# Motor_Connection.net
KiCad netlist of a schematic drawn in Altium Designer
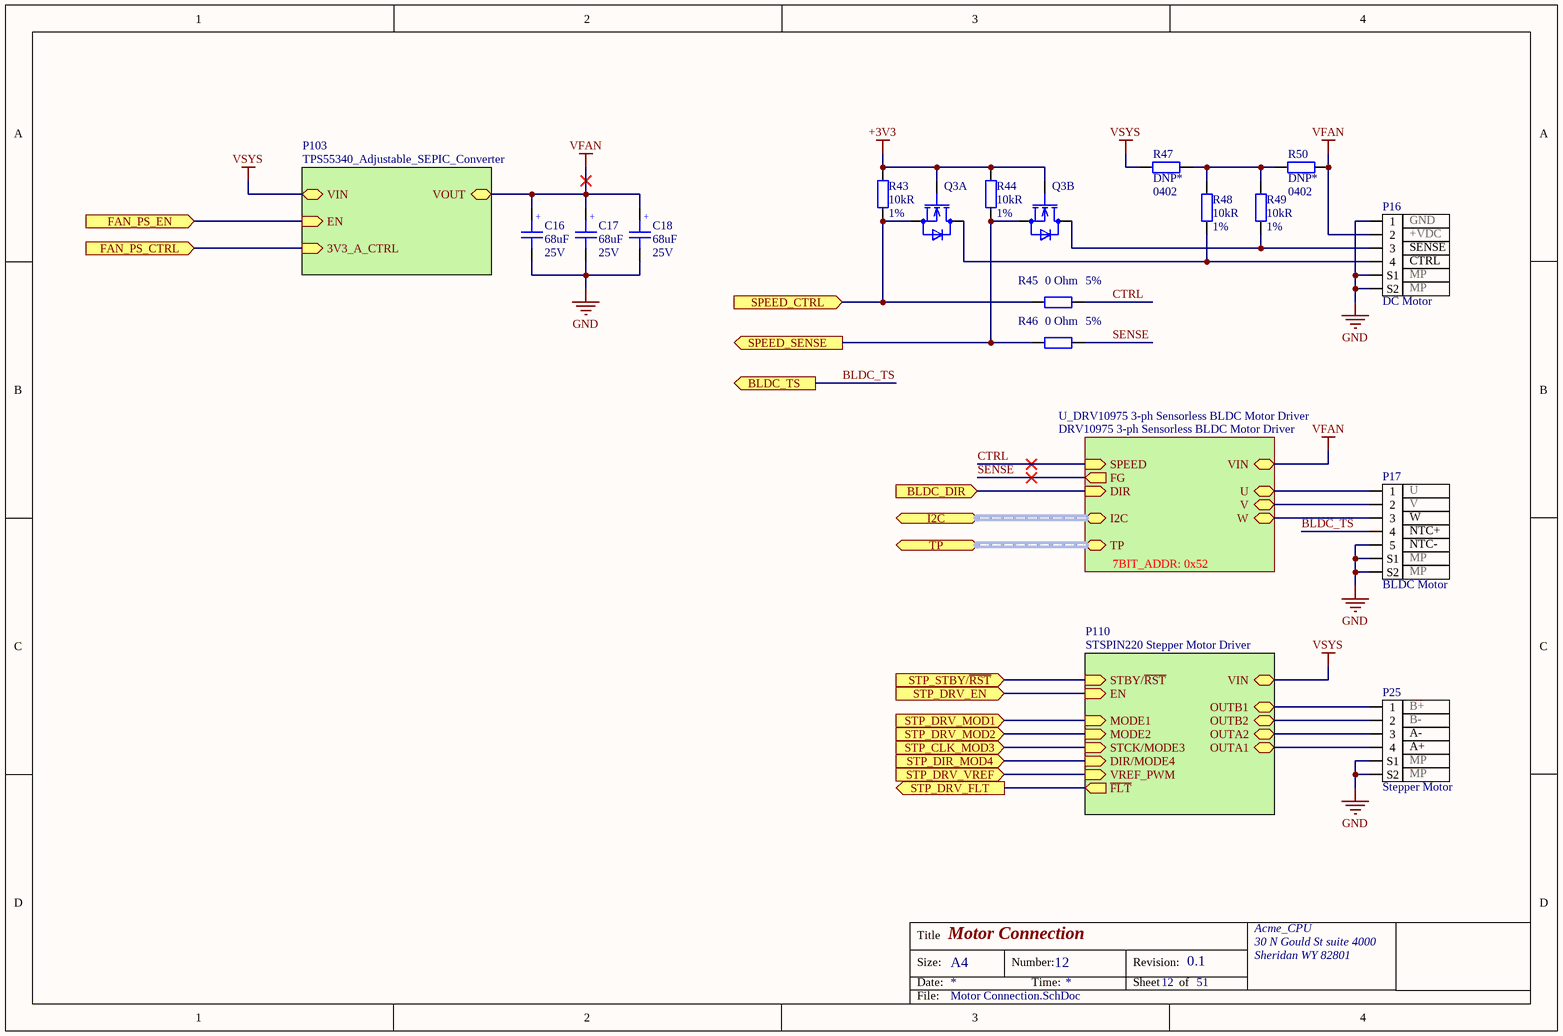
[diagram p0: Motor Connection.SchDoc]

(export (version "E")
  (design (tool "Eeschema 10.0.6"))
  (components
    (comp (ref "C16")
      (value "CAP ALUM 68 UF 20% 25 V SMD")
      (footprint "WCAP-ASLI_6.3x5.5")
      (description "68µF 25V Aluminum Electrolytic Capacitors Radial, Can - SMD  2000 Hrs @ 105°C")
      (fields
        (field (name "MANUFACTURER") "Wurth Elektronik")
        (field (name "MANUFACTURER PART NUMBER") "865080443009")
        (field (name "CAPACITANCE") "68uF")
        (field (name "RATED VOLTAGE") "25V")
      )
      (libsource (lib "capacitors_alum_electr_poly") (part "CAP ALUM 68 UF 20% 25 V SMD"))
    )
    (comp (ref "C17")
      (value "CAP ALUM 68 UF 20% 25 V SMD")
      (footprint "WCAP-ASLI_6.3x5.5")
      (description "68µF 25V Aluminum Electrolytic Capacitors Radial, Can - SMD  2000 Hrs @ 105°C")
      (fields
        (field (name "MANUFACTURER") "Wurth Elektronik")
        (field (name "MANUFACTURER PART NUMBER") "865080443009")
        (field (name "CAPACITANCE") "68uF")
        (field (name "RATED VOLTAGE") "25V")
      )
      (libsource (lib "capacitors_alum_electr_poly") (part "CAP ALUM 68 UF 20% 25 V SMD"))
    )
    (comp (ref "C18")
      (value "CAP ALUM 68 UF 20% 25 V SMD")
      (footprint "WCAP-ASLI_6.3x5.5")
      (description "68µF 25V Aluminum Electrolytic Capacitors Radial, Can - SMD  2000 Hrs @ 105°C")
      (fields
        (field (name "MANUFACTURER") "Wurth Elektronik")
        (field (name "MANUFACTURER PART NUMBER") "865080443009")
        (field (name "CAPACITANCE") "68uF")
        (field (name "RATED VOLTAGE") "25V")
      )
      (libsource (lib "capacitors_alum_electr_poly") (part "CAP ALUM 68 UF 20% 25 V SMD"))
    )
    (comp (ref "P16")
      (value "DC Motor")
      (footprint "CONN_JST_S4B-ZR-SM4A-TF(LF)(SN)")
      (description "Connector Header Surface Mount, Right Angle 4 position 0.059\" (1.50mm)")
      (fields
        (field (name "MANUFACTURER") "JST")
        (field (name "MANUFACTURER PART NUMBER") "S4B-ZR-SM4A-TF(LF)(SN)")
        (field (name "PIN_1") "GND")
        (field (name "PIN_2") "+VDC")
        (field (name "PIN_MP1") "MP")
        (field (name "PIN_MP2") "MP")
        (field (name "PIN_3") "SENSE")
        (field (name "PIN_4") "CTRL")
      )
      (libsource (lib "connectors_header") (part "CONN HEADER SMD R/A 4POS 1.5MM"))
    )
    (comp (ref "P17")
      (value "BLDC Motor")
      (footprint "CONN_JST_S5B-ZR-SM4A-TF(LF)(SN)")
      (description "Connector Header Surface Mount, Right Angle 5 position 0.059\" (1.50mm)")
      (fields
        (field (name "MANUFACTURER") "JST")
        (field (name "MANUFACTURER PART NUMBER") "S5B-ZR-SM4A-TF(LF)(SN)")
        (field (name "PIN_1") "U")
        (field (name "PIN_2") "V")
        (field (name "PIN_MP1") "MP")
        (field (name "PIN_MP2") "MP")
        (field (name "PIN_3") "W")
        (field (name "PIN_4") "NTC+")
        (field (name "PIN_5") "NTC-")
      )
      (libsource (lib "connectors_header") (part "CONN HEADER SMD R/A 5POS 1.5MM"))
    )
    (comp (ref "P25")
      (value "Stepper Motor")
      (footprint "CONN_JST_SM4B-NSHSS-TB(LF)(SN)")
      (description "Connector Header Surface Mount, Right Angle 4 position 0.039\" (1.00mm)")
      (fields
        (field (name "MANUFACTURER") "JST")
        (field (name "MANUFACTURER PART NUMBER") "SM04B-NSHSS-TB(LF)(SN)")
        (field (name "PIN_1") "B+")
        (field (name "PIN_2") "B-")
        (field (name "PIN_MP1") "MP")
        (field (name "PIN_MP2") "MP")
        (field (name "PIN_3") "A-")
        (field (name "PIN_4") "A+")
      )
      (libsource (lib "connectors_header") (part "CONN HEADER SMD R/A 4POS 1MM"))
    )
    (comp (ref "Q3")
      (value "DMN32D2LV-7")
      (footprint "SON_400UV-7_DIO")
      (description "Mosfet Array 2 N-Channel (Dual) 30V 400mA 400mW Surface Mount SOT-563")
      (fields (field (name "MANUFACTURER") "Diodes"))
      (libsource (lib "mosfets") (part "ARRAY MOSFET 2N-CH 30V 0.4A SOT-563"))
    )
    (comp (ref "R43")
      (value "RES SMD 10K OHM 1% 1/16W 0402")
      (footprint "R0402")
      (description "10 kOhms ±1% 0.063W, 1/16W Chip Resistor 0402 (1005 Metric) Moisture Resistant Thick Film")
      (fields
        (field (name "MANUFACTURER PART NUMBER") "RC0402FR-0710KP")
        (field (name "MANUFACTURER") "Yageo")
        (field (name "RESISTANCE") "10kR")
        (field (name "TOLERANCE") "1%")
      )
      (libsource (lib "resistors_smd") (part "RES SMD 10K OHM 1% 1/16W 0402"))
    )
    (comp (ref "R44")
      (value "RES SMD 10K OHM 1% 1/16W 0402")
      (footprint "R0402")
      (description "10 kOhms ±1% 0.063W, 1/16W Chip Resistor 0402 (1005 Metric) Moisture Resistant Thick Film")
      (fields
        (field (name "MANUFACTURER PART NUMBER") "RC0402FR-0710KP")
        (field (name "MANUFACTURER") "Yageo")
        (field (name "RESISTANCE") "10kR")
        (field (name "TOLERANCE") "1%")
      )
      (libsource (lib "resistors_smd") (part "RES SMD 10K OHM 1% 1/16W 0402"))
    )
    (comp (ref "R45")
      (value "RES SMD 0 OHM JUMPER 1/16W 0402")
      (footprint "R0402")
      (description "0 Ohms Jumper 0.063W, 1/16W Chip Resistor 0402 (1005 Metric) Moisture Resistant Thick Film")
      (fields
        (field (name "MANUFACTURER") "Yageo")
        (field (name "MANUFACTURER PART NUMBER") "RC0402JR-070RL")
        (field (name "TOLERANCE") "5%")
        (field (name "RESISTANCE") "0 Ohm")
      )
      (libsource (lib "resistors_smd") (part "RES SMD 0 OHM JUMPER 1/16W 0402"))
    )
    (comp (ref "R46")
      (value "RES SMD 0 OHM JUMPER 1/16W 0402")
      (footprint "R0402")
      (description "0 Ohms Jumper 0.063W, 1/16W Chip Resistor 0402 (1005 Metric) Moisture Resistant Thick Film")
      (fields
        (field (name "MANUFACTURER") "Yageo")
        (field (name "MANUFACTURER PART NUMBER") "RC0402JR-070RL")
        (field (name "TOLERANCE") "5%")
        (field (name "RESISTANCE") "0 Ohm")
      )
      (libsource (lib "resistors_smd") (part "RES SMD 0 OHM JUMPER 1/16W 0402"))
    )
    (comp (ref "R47")
      (value "DNP*")
      (footprint "R0402")
      (description "Placeholder for a 0402 resistor")
      (fields (field (name "CASE/PACKAGE") "0402"))
      (libsource (lib "resistors_smd") (part "RES SMD NO BOM 0402"))
    )
    (comp (ref "R48")
      (value "RES SMD 10K OHM 1% 1/16W 0402")
      (footprint "R0402")
      (description "10 kOhms ±1% 0.063W, 1/16W Chip Resistor 0402 (1005 Metric) Moisture Resistant Thick Film")
      (fields
        (field (name "MANUFACTURER PART NUMBER") "RC0402FR-0710KP")
        (field (name "MANUFACTURER") "Yageo")
        (field (name "RESISTANCE") "10kR")
        (field (name "TOLERANCE") "1%")
      )
      (libsource (lib "resistors_smd") (part "RES SMD 10K OHM 1% 1/16W 0402"))
    )
    (comp (ref "R49")
      (value "RES SMD 10K OHM 1% 1/16W 0402")
      (footprint "R0402")
      (description "10 kOhms ±1% 0.063W, 1/16W Chip Resistor 0402 (1005 Metric) Moisture Resistant Thick Film")
      (fields
        (field (name "MANUFACTURER PART NUMBER") "RC0402FR-0710KP")
        (field (name "MANUFACTURER") "Yageo")
        (field (name "RESISTANCE") "10kR")
        (field (name "TOLERANCE") "1%")
      )
      (libsource (lib "resistors_smd") (part "RES SMD 10K OHM 1% 1/16W 0402"))
    )
    (comp (ref "R50")
      (value "DNP*")
      (footprint "R0402")
      (description "Placeholder for a 0402 resistor")
      (fields (field (name "CASE/PACKAGE") "0402"))
      (libsource (lib "resistors_smd") (part "RES SMD NO BOM 0402"))
    )
  )
  (nets
    (net (code "3") (name "+3V3") (class "Default")
      (node (ref "Q3") (pin "2") (pinfunction "G_2") (pintype "passive"))
      (node (ref "Q3") (pin "5") (pinfunction "G_5") (pintype "passive"))
      (node (ref "R43") (pin "1") (pinfunction "1_1") (pintype "passive"))
      (node (ref "R44") (pin "1") (pinfunction "1_1") (pintype "passive"))
    )
    (net (code "5") (name "/BLDC_TS") (class "Default")
      (node (ref "P17") (pin "4") (pinfunction "4_4") (pintype "passive"))
    )
    (net (code "6") (name "/CTRL") (class "Default")
      (node (ref "R45") (pin "2") (pinfunction "2_2") (pintype "passive"))
    )
    (net (code "10") (name "/OUTA1") (class "Default")
      (node (ref "P25") (pin "4") (pinfunction "4_4") (pintype "passive"))
    )
    (net (code "11") (name "/OUTA2") (class "Default")
      (node (ref "P25") (pin "3") (pinfunction "3_3") (pintype "passive"))
    )
    (net (code "12") (name "/OUTB1") (class "Default")
      (node (ref "P25") (pin "1") (pinfunction "1_1") (pintype "passive"))
    )
    (net (code "13") (name "/OUTB2") (class "Default")
      (node (ref "P25") (pin "2") (pinfunction "2_2") (pintype "passive"))
    )
    (net (code "14") (name "/SENSE") (class "Default")
      (node (ref "R46") (pin "2") (pinfunction "2_2") (pintype "passive"))
    )
    (net (code "15") (name "/SPEED_CTRL") (class "Default")
      (node (ref "Q3") (pin "1") (pinfunction "S_1") (pintype "passive"))
      (node (ref "R43") (pin "2") (pinfunction "2_2") (pintype "passive"))
      (node (ref "R45") (pin "1") (pinfunction "1_1") (pintype "passive"))
    )
    (net (code "16") (name "/SPEED_SENSE") (class "Default")
      (node (ref "Q3") (pin "4") (pinfunction "S_4") (pintype "passive"))
      (node (ref "R44") (pin "2") (pinfunction "2_2") (pintype "passive"))
      (node (ref "R46") (pin "1") (pinfunction "1_1") (pintype "passive"))
    )
    (net (code "26") (name "/U") (class "Default")
      (node (ref "P17") (pin "1") (pinfunction "1_1") (pintype "passive"))
    )
    (net (code "27") (name "/V") (class "Default")
      (node (ref "P17") (pin "2") (pinfunction "2_2") (pintype "passive"))
    )
    (net (code "28") (name "/W") (class "Default")
      (node (ref "P17") (pin "3") (pinfunction "3_3") (pintype "passive"))
    )
    (net (code "29") (name "GND") (class "Default")
      (node (ref "C16") (pin "2") (pinfunction "2_2") (pintype "passive"))
      (node (ref "C17") (pin "2") (pinfunction "2_2") (pintype "passive"))
      (node (ref "C18") (pin "2") (pinfunction "2_2") (pintype "passive"))
      (node (ref "P16") (pin "1") (pinfunction "1_1") (pintype "passive"))
      (node (ref "P16") (pin "S1") (pinfunction "S1_S1") (pintype "passive"))
      (node (ref "P16") (pin "S2") (pinfunction "S2_S2") (pintype "passive"))
      (node (ref "P17") (pin "5") (pinfunction "5_5") (pintype "passive"))
      (node (ref "P17") (pin "S1") (pinfunction "S1_S1") (pintype "passive"))
      (node (ref "P17") (pin "S2") (pinfunction "S2_S2") (pintype "passive"))
      (node (ref "P25") (pin "S1") (pinfunction "S1_S1") (pintype "passive"))
      (node (ref "P25") (pin "S2") (pinfunction "S2_S2") (pintype "passive"))
    )
    (net (code "30") (name "Net-(Q3A-D)") (class "Default")
      (node (ref "P16") (pin "4") (pinfunction "4_4") (pintype "passive"))
      (node (ref "Q3") (pin "6") (pinfunction "D_6") (pintype "passive"))
      (node (ref "R48") (pin "2") (pinfunction "2_2") (pintype "passive"))
    )
    (net (code "31") (name "Net-(Q3B-D)") (class "Default")
      (node (ref "P16") (pin "3") (pinfunction "3_3") (pintype "passive"))
      (node (ref "Q3") (pin "3") (pinfunction "D_3") (pintype "passive"))
      (node (ref "R49") (pin "2") (pinfunction "2_2") (pintype "passive"))
    )
    (net (code "32") (name "Net-(R47-Pad2)") (class "Default")
      (node (ref "R47") (pin "2") (pinfunction "2_2") (pintype "passive"))
      (node (ref "R48") (pin "1") (pinfunction "1_1") (pintype "passive"))
      (node (ref "R49") (pin "1") (pinfunction "1_1") (pintype "passive"))
      (node (ref "R50") (pin "1") (pinfunction "1_1") (pintype "passive"))
    )
    (net (code "33") (name "VFAN") (class "Default")
      (node (ref "C16") (pin "1") (pinfunction "1_1") (pintype "passive"))
      (node (ref "C17") (pin "1") (pinfunction "1_1") (pintype "passive"))
      (node (ref "C18") (pin "1") (pinfunction "1_1") (pintype "passive"))
      (node (ref "P16") (pin "2") (pinfunction "2_2") (pintype "passive"))
      (node (ref "R50") (pin "2") (pinfunction "2_2") (pintype "passive"))
    )
    (net (code "34") (name "VSYS") (class "Default")
      (node (ref "R47") (pin "1") (pinfunction "1_1") (pintype "passive"))
    )
  )
)
